# Atari_SIO2SD_Igi_version.net
KiCad netlist of a schematic drawn in EAGLE
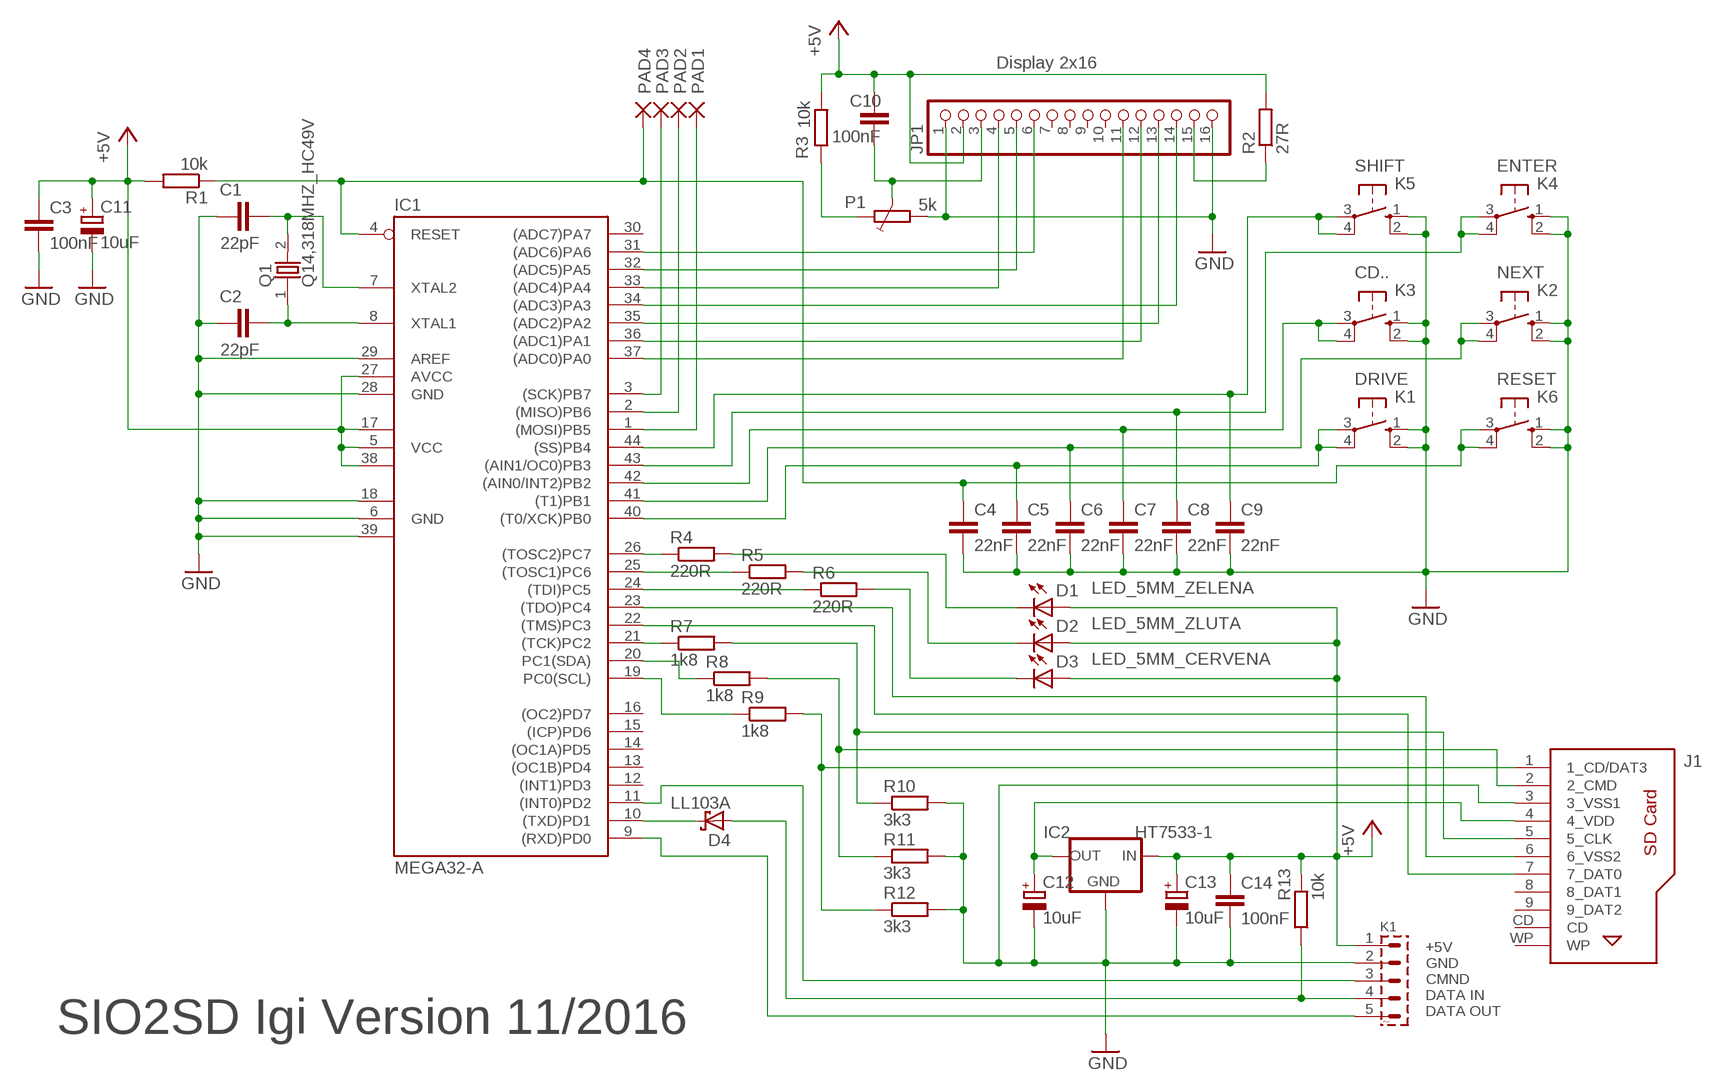
[diagram p0: schematic, sheet 1]

(export (version "E")
  (design (tool "Eeschema 10.0.6"))
  (components
    (comp (ref "C1")
      (value "22pF")
      (footprint "eagle-import:1206")
      (libsource (lib "eagle-import") (part "C-SMD1206"))
    )
    (comp (ref "C2")
      (value "22pF")
      (footprint "eagle-import:1206")
      (libsource (lib "eagle-import") (part "C-SMD1206"))
    )
    (comp (ref "C3")
      (value "100nF")
      (footprint "eagle-import:1206")
      (libsource (lib "eagle-import") (part "C-SMD1206"))
    )
    (comp (ref "C4")
      (value "22nF")
      (footprint "eagle-import:1206")
      (libsource (lib "eagle-import") (part "C-SMD1206"))
    )
    (comp (ref "C5")
      (value "22nF")
      (footprint "eagle-import:1206")
      (libsource (lib "eagle-import") (part "C-SMD1206"))
    )
    (comp (ref "C6")
      (value "22nF")
      (footprint "eagle-import:1206")
      (libsource (lib "eagle-import") (part "C-SMD1206"))
    )
    (comp (ref "C7")
      (value "22nF")
      (footprint "eagle-import:1206")
      (libsource (lib "eagle-import") (part "C-SMD1206"))
    )
    (comp (ref "C8")
      (value "22nF")
      (footprint "eagle-import:1206")
      (libsource (lib "eagle-import") (part "C-SMD1206"))
    )
    (comp (ref "C9")
      (value "22nF")
      (footprint "eagle-import:1206")
      (libsource (lib "eagle-import") (part "C-SMD1206"))
    )
    (comp (ref "C10")
      (value "100nF")
      (footprint "eagle-import:1206")
      (libsource (lib "eagle-import") (part "C-SMD1206"))
    )
    (comp (ref "C11")
      (value "10uF")
      (footprint "eagle-import:A_3216")
      (libsource (lib "eagle-import") (part "CTSA"))
    )
    (comp (ref "C12")
      (value "10uF")
      (footprint "eagle-import:A_3216")
      (libsource (lib "eagle-import") (part "CTSA"))
    )
    (comp (ref "C13")
      (value "10uF")
      (footprint "eagle-import:A_3216")
      (libsource (lib "eagle-import") (part "CTSA"))
    )
    (comp (ref "C14")
      (value "100nF")
      (footprint "eagle-import:1206")
      (libsource (lib "eagle-import") (part "C-SMD1206"))
    )
    (comp (ref "CD..")
      (value "K3")
      (footprint "eagle-import:B3F-10XX")
      (fields (field (name "MPN") "B3F-1000"))
      (libsource (lib "eagle-import") (part "10-XX"))
    )
    (comp (ref "D1")
      (value "LED_5MM_ZELENA")
      (footprint "eagle-import:A5,0")
      (libsource (lib "eagle-import") (part "LED_5MM_ZELENA"))
    )
    (comp (ref "D2")
      (value "LED_5MM_ZLUTA")
      (footprint "eagle-import:A5,0")
      (libsource (lib "eagle-import") (part "LED_5MM_ZLUTA"))
    )
    (comp (ref "D3")
      (value "LED_5MM_CERVENA")
      (footprint "eagle-import:A5,0")
      (libsource (lib "eagle-import") (part "LED_5MM_CERVENA"))
    )
    (comp (ref "D4")
      (value "LL103A")
      (footprint "eagle-import:MINIMELF")
      (libsource (lib "eagle-import") (part "LL103A"))
    )
    (comp (ref "DRIVE")
      (value "K1")
      (footprint "eagle-import:B3F-10XX")
      (fields (field (name "MPN") "B3F-1000"))
      (libsource (lib "eagle-import") (part "10-XX"))
    )
    (comp (ref "ENTER")
      (value "K4")
      (footprint "eagle-import:B3F-10XX")
      (fields (field (name "MPN") "B3F-1000"))
      (libsource (lib "eagle-import") (part "10-XX"))
    )
    (comp (ref "IC1")
      (value "MEGA32-A")
      (footprint "eagle-import:TQFP44")
      (fields (field (name "MPN") "ATMEGA32-16AU"))
      (libsource (lib "eagle-import") (part "MEGA32-A"))
    )
    (comp (ref "IC2")
      (value "HT7533-1")
      (footprint "eagle-import:SOT89R")
      (libsource (lib "eagle-import") (part "HT7533-1_SMD"))
    )
    (comp (ref "J1")
      (value "693061010911")
      (footprint "eagle-import:693061010911")
      (libsource (lib "eagle-import") (part "693061010911"))
    )
    (comp (ref "JP1")
      (value "Display 2x16")
      (footprint "eagle-import:1X16")
      (libsource (lib "eagle-import") (part "PINHD-1X16"))
    )
    (comp (ref "K1")
      (value "PSH02-05W")
      (footprint "eagle-import:PSH02-05W")
      (libsource (lib "eagle-import") (part "PSH02-05W"))
    )
    (comp (ref "NEXT")
      (value "K2")
      (footprint "eagle-import:B3F-10XX")
      (fields (field (name "MPN") "B3F-1000"))
      (libsource (lib "eagle-import") (part "10-XX"))
    )
    (comp (ref "P1")
      (value "5k")
      (footprint "eagle-import:3362P")
      (libsource (lib "eagle-import") (part "3362P"))
    )
    (comp (ref "PAD1")
      (value "SMD2")
      (footprint "eagle-import:SMD1,27-2,54")
      (libsource (lib "eagle-import") (part "SMD2"))
    )
    (comp (ref "PAD2")
      (value "SMD2")
      (footprint "eagle-import:SMD1,27-2,54")
      (libsource (lib "eagle-import") (part "SMD2"))
    )
    (comp (ref "PAD3")
      (value "SMD2")
      (footprint "eagle-import:SMD1,27-2,54")
      (libsource (lib "eagle-import") (part "SMD2"))
    )
    (comp (ref "PAD4")
      (value "SMD2")
      (footprint "eagle-import:SMD1,27-2,54")
      (libsource (lib "eagle-import") (part "SMD2"))
    )
    (comp (ref "Q1")
      (value "Q14,318MHZ_HC49V")
      (footprint "eagle-import:HC49U-V")
      (libsource (lib "eagle-import") (part "Q14,318MHZ_HC49V"))
    )
    (comp (ref "R1")
      (value "10k")
      (footprint "eagle-import:R1206")
      (libsource (lib "eagle-import") (part "R1206"))
    )
    (comp (ref "R2")
      (value "27R")
      (footprint "eagle-import:R1206")
      (libsource (lib "eagle-import") (part "R1206"))
    )
    (comp (ref "R3")
      (value "10k")
      (footprint "eagle-import:R1206")
      (libsource (lib "eagle-import") (part "R1206"))
    )
    (comp (ref "R4")
      (value "220R")
      (footprint "eagle-import:R1206")
      (libsource (lib "eagle-import") (part "R1206"))
    )
    (comp (ref "R5")
      (value "220R")
      (footprint "eagle-import:R1206")
      (libsource (lib "eagle-import") (part "R1206"))
    )
    (comp (ref "R6")
      (value "220R")
      (footprint "eagle-import:R1206")
      (libsource (lib "eagle-import") (part "R1206"))
    )
    (comp (ref "R7")
      (value "1k8")
      (footprint "eagle-import:R1206")
      (libsource (lib "eagle-import") (part "R1206"))
    )
    (comp (ref "R8")
      (value "1k8")
      (footprint "eagle-import:R1206")
      (libsource (lib "eagle-import") (part "R1206"))
    )
    (comp (ref "R9")
      (value "1k8")
      (footprint "eagle-import:R1206")
      (libsource (lib "eagle-import") (part "R1206"))
    )
    (comp (ref "R10")
      (value "3k3")
      (footprint "eagle-import:R1206")
      (libsource (lib "eagle-import") (part "R1206"))
    )
    (comp (ref "R11")
      (value "3k3")
      (footprint "eagle-import:R1206")
      (libsource (lib "eagle-import") (part "R1206"))
    )
    (comp (ref "R12")
      (value "3k3")
      (footprint "eagle-import:R1206")
      (libsource (lib "eagle-import") (part "R1206"))
    )
    (comp (ref "R13")
      (value "10k")
      (footprint "eagle-import:R1206")
      (libsource (lib "eagle-import") (part "R1206"))
    )
    (comp (ref "RESET")
      (value "K6")
      (footprint "eagle-import:B3F-10XX")
      (fields (field (name "MPN") "B3F-1000"))
      (libsource (lib "eagle-import") (part "10-XX"))
    )
    (comp (ref "SHIFT")
      (value "K5")
      (footprint "eagle-import:B3F-10XX")
      (fields (field (name "MPN") "B3F-1000"))
      (libsource (lib "eagle-import") (part "10-XX"))
    )
  )
  (nets
    (net (code "1") (name "+5V") (class "Default")
      (node (ref "C10") (pin "1") (pinfunction "1_1") (pintype "passive"))
      (node (ref "C11") (pin "+") (pinfunction "+_+") (pintype "passive"))
      (node (ref "C13") (pin "+") (pinfunction "+_+") (pintype "passive"))
      (node (ref "C14") (pin "1") (pinfunction "1_1") (pintype "passive"))
      (node (ref "C3") (pin "1") (pinfunction "1_1") (pintype "passive"))
      (node (ref "D1") (pin "A") (pinfunction "A_A") (pintype "passive"))
      (node (ref "D2") (pin "A") (pinfunction "A_A") (pintype "passive"))
      (node (ref "D3") (pin "A") (pinfunction "A_A") (pintype "passive"))
      (node (ref "IC1") (pin "17") (pinfunction "VCC1_17") (pintype "power_in"))
      (node (ref "IC1") (pin "27") (pinfunction "AVCC_27") (pintype "power_in"))
      (node (ref "IC1") (pin "38") (pinfunction "VCC2_38") (pintype "power_in"))
      (node (ref "IC1") (pin "5") (pinfunction "VCC_5") (pintype "power_in"))
      (node (ref "IC2") (pin "2") (pinfunction "IN_2") (pintype "input"))
      (node (ref "IC2") (pin "4") (pinfunction "IN_4") (pintype "input"))
      (node (ref "JP1") (pin "2") (pinfunction "2_2") (pintype "passive"))
      (node (ref "K1") (pin "1") (pinfunction "1_1") (pintype "passive"))
      (node (ref "R1") (pin "2") (pinfunction "2_2") (pintype "passive"))
      (node (ref "R13") (pin "2") (pinfunction "2_2") (pintype "passive"))
      (node (ref "R2") (pin "2") (pinfunction "2_2") (pintype "passive"))
      (node (ref "R3") (pin "1") (pinfunction "1_1") (pintype "passive"))
    )
    (net (code "2") (name "GND") (class "Default")
      (node (ref "C1") (pin "1") (pinfunction "1_1") (pintype "passive"))
      (node (ref "C11") (pin "-") (pinfunction "-_-") (pintype "passive"))
      (node (ref "C12") (pin "-") (pinfunction "-_-") (pintype "passive"))
      (node (ref "C13") (pin "-") (pinfunction "-_-") (pintype "passive"))
      (node (ref "C14") (pin "2") (pinfunction "2_2") (pintype "passive"))
      (node (ref "C2") (pin "1") (pinfunction "1_1") (pintype "passive"))
      (node (ref "C3") (pin "2") (pinfunction "2_2") (pintype "passive"))
      (node (ref "C4") (pin "2") (pinfunction "2_2") (pintype "passive"))
      (node (ref "C5") (pin "2") (pinfunction "2_2") (pintype "passive"))
      (node (ref "C6") (pin "2") (pinfunction "2_2") (pintype "passive"))
      (node (ref "C7") (pin "2") (pinfunction "2_2") (pintype "passive"))
      (node (ref "C8") (pin "2") (pinfunction "2_2") (pintype "passive"))
      (node (ref "C9") (pin "2") (pinfunction "2_2") (pintype "passive"))
      (node (ref "CD..") (pin "1") (pinfunction "S_1") (pintype "passive"))
      (node (ref "CD..") (pin "2") (pinfunction "S1_2") (pintype "passive"))
      (node (ref "DRIVE") (pin "1") (pinfunction "S_1") (pintype "passive"))
      (node (ref "DRIVE") (pin "2") (pinfunction "S1_2") (pintype "passive"))
      (node (ref "ENTER") (pin "1") (pinfunction "S_1") (pintype "passive"))
      (node (ref "ENTER") (pin "2") (pinfunction "S1_2") (pintype "passive"))
      (node (ref "IC1") (pin "18") (pinfunction "GND1_18") (pintype "power_in"))
      (node (ref "IC1") (pin "28") (pinfunction "GND_28") (pintype "power_in"))
      (node (ref "IC1") (pin "29") (pinfunction "AREF_29") (pintype "passive"))
      (node (ref "IC1") (pin "39") (pinfunction "GND2_39") (pintype "power_in"))
      (node (ref "IC1") (pin "6") (pinfunction "GND_6") (pintype "power_in"))
      (node (ref "IC2") (pin "1") (pinfunction "GND_1") (pintype "input"))
      (node (ref "J1") (pin "3") (pinfunction "3_VSS1_3") (pintype "bidirectional"))
      (node (ref "JP1") (pin "1") (pinfunction "1_1") (pintype "passive"))
      (node (ref "JP1") (pin "16") (pinfunction "16_16") (pintype "passive"))
      (node (ref "K1") (pin "2") (pinfunction "2_2") (pintype "passive"))
      (node (ref "NEXT") (pin "1") (pinfunction "S_1") (pintype "passive"))
      (node (ref "NEXT") (pin "2") (pinfunction "S1_2") (pintype "passive"))
      (node (ref "P1") (pin "A") (pinfunction "1_A") (pintype "passive"))
      (node (ref "R10") (pin "2") (pinfunction "2_2") (pintype "passive"))
      (node (ref "R11") (pin "2") (pinfunction "2_2") (pintype "passive"))
      (node (ref "R12") (pin "2") (pinfunction "2_2") (pintype "passive"))
      (node (ref "RESET") (pin "1") (pinfunction "S_1") (pintype "passive"))
      (node (ref "RESET") (pin "2") (pinfunction "S1_2") (pintype "passive"))
      (node (ref "SHIFT") (pin "1") (pinfunction "S_1") (pintype "passive"))
      (node (ref "SHIFT") (pin "2") (pinfunction "S1_2") (pintype "passive"))
    )
    (net (code "3") (name "Net-(CD..-P)") (class "Default")
      (node (ref "C7") (pin "1") (pinfunction "1_1") (pintype "passive"))
      (node (ref "CD..") (pin "3") (pinfunction "P_3") (pintype "passive"))
      (node (ref "CD..") (pin "4") (pinfunction "P1_4") (pintype "passive"))
      (node (ref "IC1") (pin "42") (pinfunction "(AIN0/INT2)PB2_42") (pintype "bidirectional"))
    )
    (net (code "4") (name "Net-(D1-C)") (class "Default")
      (node (ref "D1") (pin "K") (pinfunction "C_K") (pintype "passive"))
      (node (ref "R4") (pin "2") (pinfunction "2_2") (pintype "passive"))
    )
    (net (code "5") (name "Net-(D2-C)") (class "Default")
      (node (ref "D2") (pin "K") (pinfunction "C_K") (pintype "passive"))
      (node (ref "R5") (pin "2") (pinfunction "2_2") (pintype "passive"))
    )
    (net (code "6") (name "Net-(D3-C)") (class "Default")
      (node (ref "D3") (pin "K") (pinfunction "C_K") (pintype "passive"))
      (node (ref "R6") (pin "2") (pinfunction "2_2") (pintype "passive"))
    )
    (net (code "7") (name "Net-(D4-PadA)") (class "Default")
      (node (ref "D4") (pin "A") (pinfunction "A_A") (pintype "passive"))
      (node (ref "K1") (pin "4") (pinfunction "4_4") (pintype "passive"))
      (node (ref "R13") (pin "1") (pinfunction "1_1") (pintype "passive"))
    )
    (net (code "8") (name "Net-(DRIVE-P)") (class "Default")
      (node (ref "C5") (pin "1") (pinfunction "1_1") (pintype "passive"))
      (node (ref "DRIVE") (pin "3") (pinfunction "P_3") (pintype "passive"))
      (node (ref "DRIVE") (pin "4") (pinfunction "P1_4") (pintype "passive"))
      (node (ref "IC1") (pin "40") (pinfunction "(T0/XCK)PB0_40") (pintype "bidirectional"))
    )
    (net (code "9") (name "Net-(ENTER-P)") (class "Default")
      (node (ref "C8") (pin "1") (pinfunction "1_1") (pintype "passive"))
      (node (ref "ENTER") (pin "3") (pinfunction "P_3") (pintype "passive"))
      (node (ref "ENTER") (pin "4") (pinfunction "P1_4") (pintype "passive"))
      (node (ref "IC1") (pin "43") (pinfunction "(AIN1/OC0)PB3_43") (pintype "bidirectional"))
    )
    (net (code "10") (name "Net-(IC1-(ADC0)PA0)") (class "Default")
      (node (ref "IC1") (pin "37") (pinfunction "(ADC0)PA0_37") (pintype "bidirectional"))
      (node (ref "JP1") (pin "11") (pinfunction "11_11") (pintype "passive"))
    )
    (net (code "11") (name "Net-(IC1-(ADC1)PA1)") (class "Default")
      (node (ref "IC1") (pin "36") (pinfunction "(ADC1)PA1_36") (pintype "bidirectional"))
      (node (ref "JP1") (pin "12") (pinfunction "12_12") (pintype "passive"))
    )
    (net (code "12") (name "Net-(IC1-(ADC2)PA2)") (class "Default")
      (node (ref "IC1") (pin "35") (pinfunction "(ADC2)PA2_35") (pintype "bidirectional"))
      (node (ref "JP1") (pin "13") (pinfunction "13_13") (pintype "passive"))
    )
    (net (code "13") (name "Net-(IC1-(ADC3)PA3)") (class "Default")
      (node (ref "IC1") (pin "34") (pinfunction "(ADC3)PA3_34") (pintype "bidirectional"))
      (node (ref "JP1") (pin "14") (pinfunction "14_14") (pintype "passive"))
    )
    (net (code "14") (name "Net-(IC1-(ADC4)PA4)") (class "Default")
      (node (ref "IC1") (pin "33") (pinfunction "(ADC4)PA4_33") (pintype "bidirectional"))
      (node (ref "JP1") (pin "4") (pinfunction "4_4") (pintype "passive"))
    )
    (net (code "15") (name "Net-(IC1-(ADC5)PA5)") (class "Default")
      (node (ref "IC1") (pin "32") (pinfunction "(ADC5)PA5_32") (pintype "bidirectional"))
      (node (ref "JP1") (pin "5") (pinfunction "5_5") (pintype "passive"))
    )
    (net (code "16") (name "Net-(IC1-(ADC6)PA6)") (class "Default")
      (node (ref "IC1") (pin "31") (pinfunction "(ADC6)PA6_31") (pintype "bidirectional"))
      (node (ref "JP1") (pin "6") (pinfunction "6_6") (pintype "passive"))
    )
    (net (code "17") (name "Net-(IC1-(INT0)PD2)") (class "Default")
      (node (ref "IC1") (pin "11") (pinfunction "(INT0)PD2_11") (pintype "bidirectional"))
      (node (ref "K1") (pin "3") (pinfunction "3_3") (pintype "passive"))
    )
    (net (code "18") (name "Net-(IC1-(MISO)PB6)") (class "Default")
      (node (ref "IC1") (pin "2") (pinfunction "(MISO)PB6_2") (pintype "bidirectional"))
      (node (ref "PAD2") (pin "1") (pinfunction "P_1") (pintype "passive"))
    )
    (net (code "19") (name "Net-(IC1-(MOSI)PB5)") (class "Default")
      (node (ref "IC1") (pin "1") (pinfunction "(MOSI)PB5_1") (pintype "bidirectional"))
      (node (ref "PAD1") (pin "1") (pinfunction "P_1") (pintype "passive"))
    )
    (net (code "20") (name "Net-(IC1-(RXD)PD0)") (class "Default")
      (node (ref "IC1") (pin "9") (pinfunction "(RXD)PD0_9") (pintype "bidirectional"))
      (node (ref "K1") (pin "5") (pinfunction "5_5") (pintype "passive"))
    )
    (net (code "21") (name "Net-(IC1-(SCK)PB7)") (class "Default")
      (node (ref "IC1") (pin "3") (pinfunction "(SCK)PB7_3") (pintype "bidirectional"))
      (node (ref "PAD3") (pin "1") (pinfunction "P_1") (pintype "passive"))
    )
    (net (code "22") (name "Net-(IC1-(SS)PB4)") (class "Default")
      (node (ref "C9") (pin "1") (pinfunction "1_1") (pintype "passive"))
      (node (ref "IC1") (pin "44") (pinfunction "(SS)PB4_44") (pintype "bidirectional"))
      (node (ref "SHIFT") (pin "3") (pinfunction "P_3") (pintype "passive"))
      (node (ref "SHIFT") (pin "4") (pinfunction "P1_4") (pintype "passive"))
    )
    (net (code "23") (name "Net-(IC1-(T1)PB1)") (class "Default")
      (node (ref "C6") (pin "1") (pinfunction "1_1") (pintype "passive"))
      (node (ref "IC1") (pin "41") (pinfunction "(T1)PB1_41") (pintype "bidirectional"))
      (node (ref "NEXT") (pin "3") (pinfunction "P_3") (pintype "passive"))
      (node (ref "NEXT") (pin "4") (pinfunction "P1_4") (pintype "passive"))
    )
    (net (code "24") (name "Net-(IC1-(TCK)PC2)") (class "Default")
      (node (ref "IC1") (pin "21") (pinfunction "(TCK)PC2_21") (pintype "bidirectional"))
      (node (ref "R7") (pin "1") (pinfunction "1_1") (pintype "passive"))
    )
    (net (code "25") (name "Net-(IC1-(TDI)PC5)") (class "Default")
      (node (ref "IC1") (pin "24") (pinfunction "(TDI)PC5_24") (pintype "bidirectional"))
      (node (ref "R6") (pin "1") (pinfunction "1_1") (pintype "passive"))
    )
    (net (code "26") (name "Net-(IC1-(TDO)PC4)") (class "Default")
      (node (ref "IC1") (pin "23") (pinfunction "(TDO)PC4_23") (pintype "bidirectional"))
      (node (ref "J1") (pin "6") (pinfunction "6_VSS2_6") (pintype "bidirectional"))
    )
    (net (code "27") (name "Net-(IC1-(TMS)PC3)") (class "Default")
      (node (ref "IC1") (pin "22") (pinfunction "(TMS)PC3_22") (pintype "bidirectional"))
      (node (ref "J1") (pin "7") (pinfunction "7_DAT0_7") (pintype "bidirectional"))
    )
    (net (code "28") (name "Net-(IC1-(TOSC1)PC6)") (class "Default")
      (node (ref "IC1") (pin "25") (pinfunction "(TOSC1)PC6_25") (pintype "bidirectional"))
      (node (ref "R5") (pin "1") (pinfunction "1_1") (pintype "passive"))
    )
    (net (code "29") (name "Net-(IC1-(TOSC2)PC7)") (class "Default")
      (node (ref "IC1") (pin "26") (pinfunction "(TOSC2)PC7_26") (pintype "bidirectional"))
      (node (ref "R4") (pin "1") (pinfunction "1_1") (pintype "passive"))
    )
    (net (code "30") (name "Net-(IC1-(TXD)PD1)") (class "Default")
      (node (ref "D4") (pin "C") (pinfunction "C_C") (pintype "passive"))
      (node (ref "IC1") (pin "10") (pinfunction "(TXD)PD1_10") (pintype "bidirectional"))
    )
    (net (code "31") (name "Net-(IC1-PC0(SCL))") (class "Default")
      (node (ref "IC1") (pin "19") (pinfunction "PC0(SCL)_19") (pintype "bidirectional"))
      (node (ref "R9") (pin "1") (pinfunction "1_1") (pintype "passive"))
    )
    (net (code "32") (name "Net-(IC1-PC1(SDA))") (class "Default")
      (node (ref "IC1") (pin "20") (pinfunction "PC1(SDA)_20") (pintype "bidirectional"))
      (node (ref "R8") (pin "1") (pinfunction "1_1") (pintype "passive"))
    )
    (net (code "33") (name "Net-(IC1-RESET)") (class "Default")
      (node (ref "C4") (pin "1") (pinfunction "1_1") (pintype "passive"))
      (node (ref "IC1") (pin "4") (pinfunction "RESET_4") (pintype "input"))
      (node (ref "PAD4") (pin "1") (pinfunction "P_1") (pintype "passive"))
      (node (ref "R1") (pin "1") (pinfunction "1_1") (pintype "passive"))
      (node (ref "RESET") (pin "3") (pinfunction "P_3") (pintype "passive"))
      (node (ref "RESET") (pin "4") (pinfunction "P1_4") (pintype "passive"))
    )
    (net (code "34") (name "Net-(IC1-XTAL1)") (class "Default")
      (node (ref "C2") (pin "2") (pinfunction "2_2") (pintype "passive"))
      (node (ref "IC1") (pin "8") (pinfunction "XTAL1_8") (pintype "bidirectional"))
      (node (ref "Q1") (pin "1") (pinfunction "1_1") (pintype "passive"))
    )
    (net (code "35") (name "Net-(IC1-XTAL2)") (class "Default")
      (node (ref "C1") (pin "2") (pinfunction "2_2") (pintype "passive"))
      (node (ref "IC1") (pin "7") (pinfunction "XTAL2_7") (pintype "bidirectional"))
      (node (ref "Q1") (pin "2") (pinfunction "2_2") (pintype "passive"))
    )
    (net (code "36") (name "Net-(IC2-OUT)") (class "Default")
      (node (ref "C12") (pin "+") (pinfunction "+_+") (pintype "passive"))
      (node (ref "IC2") (pin "3") (pinfunction "OUT_3") (pintype "passive"))
      (node (ref "J1") (pin "4") (pinfunction "4_VDD_4") (pintype "bidirectional"))
    )
    (net (code "37") (name "Net-(J1-1_CD{slash}DAT3)") (class "Default")
      (node (ref "J1") (pin "1") (pinfunction "1_CD/DAT3_1") (pintype "bidirectional"))
      (node (ref "R12") (pin "1") (pinfunction "1_1") (pintype "passive"))
      (node (ref "R9") (pin "2") (pinfunction "2_2") (pintype "passive"))
    )
    (net (code "38") (name "Net-(J1-2_CMD)") (class "Default")
      (node (ref "J1") (pin "2") (pinfunction "2_CMD_2") (pintype "bidirectional"))
      (node (ref "R11") (pin "1") (pinfunction "1_1") (pintype "passive"))
      (node (ref "R8") (pin "2") (pinfunction "2_2") (pintype "passive"))
    )
    (net (code "39") (name "Net-(J1-5_CLK)") (class "Default")
      (node (ref "J1") (pin "5") (pinfunction "5_CLK_5") (pintype "bidirectional"))
      (node (ref "R10") (pin "1") (pinfunction "1_1") (pintype "passive"))
      (node (ref "R7") (pin "2") (pinfunction "2_2") (pintype "passive"))
    )
    (net (code "40") (name "Net-(JP1-Pad15)") (class "Default")
      (node (ref "JP1") (pin "15") (pinfunction "15_15") (pintype "passive"))
      (node (ref "R2") (pin "1") (pinfunction "1_1") (pintype "passive"))
    )
    (net (code "41") (name "Net-(P1-2)") (class "Default")
      (node (ref "P1") (pin "E") (pinfunction "2_E") (pintype "passive"))
      (node (ref "R3") (pin "2") (pinfunction "2_2") (pintype "passive"))
    )
    (net (code "42") (name "Net-(P1-3)") (class "Default")
      (node (ref "C10") (pin "2") (pinfunction "2_2") (pintype "passive"))
      (node (ref "JP1") (pin "3") (pinfunction "3_3") (pintype "passive"))
      (node (ref "P1") (pin "S") (pinfunction "3_S") (pintype "passive"))
    )
    (net (code "43") (name "unconnected-(IC1-(ADC7)PA7-Pad30)") (class "Default")
      (node (ref "IC1") (pin "30") (pinfunction "(ADC7)PA7_30") (pintype "bidirectional"))
    )
    (net (code "44") (name "unconnected-(IC1-(ICP)PD6-Pad15)") (class "Default")
      (node (ref "IC1") (pin "15") (pinfunction "(ICP)PD6_15") (pintype "bidirectional"))
    )
    (net (code "45") (name "unconnected-(IC1-(INT1)PD3-Pad12)") (class "Default")
      (node (ref "IC1") (pin "12") (pinfunction "(INT1)PD3_12") (pintype "bidirectional"))
    )
    (net (code "46") (name "unconnected-(IC1-(OC1A)PD5-Pad14)") (class "Default")
      (node (ref "IC1") (pin "14") (pinfunction "(OC1A)PD5_14") (pintype "bidirectional"))
    )
    (net (code "47") (name "unconnected-(IC1-(OC1B)PD4-Pad13)") (class "Default")
      (node (ref "IC1") (pin "13") (pinfunction "(OC1B)PD4_13") (pintype "bidirectional"))
    )
    (net (code "48") (name "unconnected-(IC1-(OC2)PD7-Pad16)") (class "Default")
      (node (ref "IC1") (pin "16") (pinfunction "(OC2)PD7_16") (pintype "bidirectional"))
    )
    (net (code "49") (name "unconnected-(J1-8_DAT1-Pad8)") (class "Default")
      (node (ref "J1") (pin "8") (pinfunction "8_DAT1_8") (pintype "bidirectional"))
    )
    (net (code "50") (name "unconnected-(J1-9_DAT2-Pad9)") (class "Default")
      (node (ref "J1") (pin "9") (pinfunction "9_DAT2_9") (pintype "bidirectional"))
    )
    (net (code "51") (name "unconnected-(J1-PadCD)") (class "Default")
      (node (ref "J1") (pin "CD") (pinfunction "CD_CD") (pintype "bidirectional"))
    )
    (net (code "52") (name "unconnected-(J1-PadWP)") (class "Default")
      (node (ref "J1") (pin "WP") (pinfunction "WP_WP") (pintype "bidirectional"))
    )
    (net (code "53") (name "unconnected-(JP1-Pad7)") (class "Default")
      (node (ref "JP1") (pin "7") (pinfunction "7_7") (pintype "passive"))
    )
    (net (code "54") (name "unconnected-(JP1-Pad8)") (class "Default")
      (node (ref "JP1") (pin "8") (pinfunction "8_8") (pintype "passive"))
    )
    (net (code "55") (name "unconnected-(JP1-Pad9)") (class "Default")
      (node (ref "JP1") (pin "9") (pinfunction "9_9") (pintype "passive"))
    )
    (net (code "56") (name "unconnected-(JP1-Pad10)") (class "Default")
      (node (ref "JP1") (pin "10") (pinfunction "10_10") (pintype "passive"))
    )
  )
)
